# Archimedes_Isil_Mosfet_Kati.net
KiCad netlist of a schematic drawn in Altium Designer
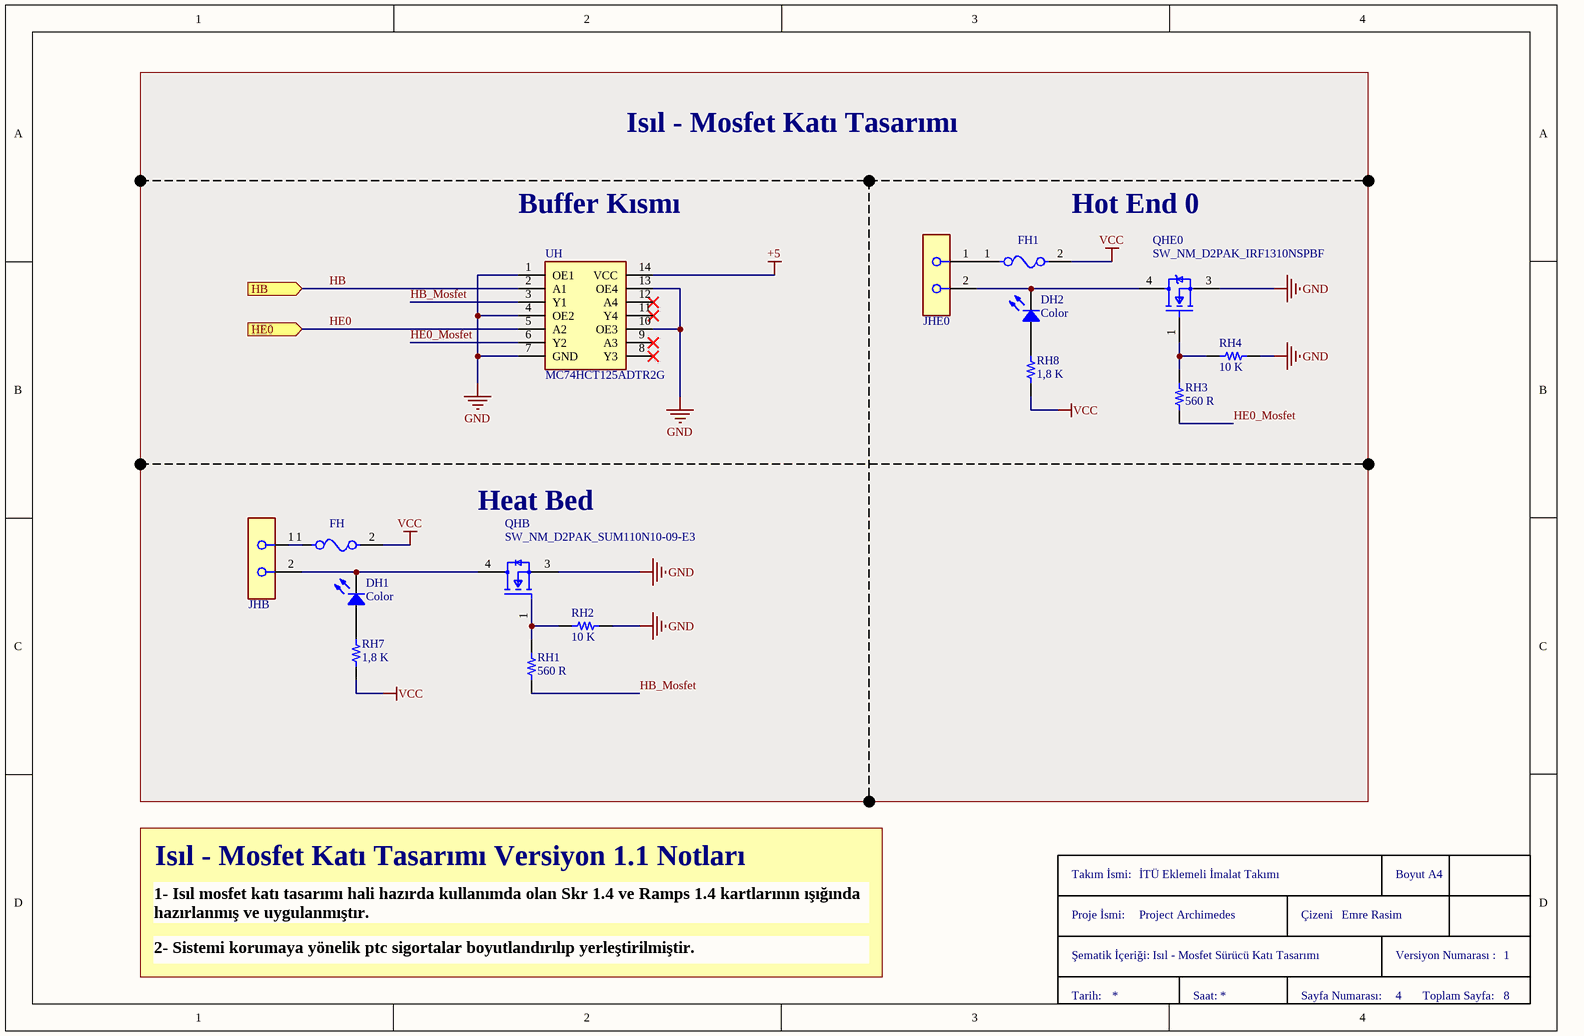
[diagram p0: Archimedes_Isil_Mosfet_Kati.SchDoc]

(export (version "E")
  (design (tool "Eeschema 10.0.6"))
  (components
    (comp (ref "DH1")
      (value "Color")
      (footprint "LED 0805/2012 GREEN")
      (description "LED 805")
      (libsource (lib "Pasifler") (part "LED 805"))
    )
    (comp (ref "DH2")
      (value "Color")
      (footprint "LED 0805/2012 GREEN")
      (description "LED 805")
      (libsource (lib "Pasifler") (part "LED 805"))
    )
    (comp (ref "FH")
      (value "VR_PTC_FRU900-30F")
      (footprint "VR_PTC_FRU900-30F")
      (description "Ptc Fuse with 9 Amper hold and 18 Amper trip values")
      (libsource (lib "EKIM_Team_Main") (part "VR_PTC_FRU900-30F"))
    )
    (comp (ref "FH1")
      (value "VR_PTC_FRU300-30F")
      (footprint "VR_PTC_FRU300-30F")
      (description "Ptc Fuse with 3 Amper hold and 6 Amper Trip values")
      (libsource (lib "EKIM_Team_Main") (part "VR_PTC_FRU300-30F"))
    )
    (comp (ref "JHB")
      (value "Con_5mm_2 lead")
      (footprint "Con_5mm_2lead")
      (description "TERM BLOCK 2POS SIDE ENTRY 5MM")
      (libsource (lib "EKIM_Team_Main") (part "Con_5mm_2 lead"))
    )
    (comp (ref "JHE0")
      (value "Con_5mm_2 lead")
      (footprint "Con_5mm_2lead")
      (description "TERM BLOCK 2POS SIDE ENTRY 5MM")
      (libsource (lib "EKIM_Team_Main") (part "Con_5mm_2 lead"))
    )
    (comp (ref "QHB")
      (value "SW_NM_D2PAK_SUM110N10-09-E3")
      (footprint "SW_D2PAK_Vishay_SUM110N10-09")
      (description "Vishay SUM110N10 nmos with d2pak package , 100 volt and 110 amper values")
      (libsource (lib "EKIM_Team_Main") (part "SW_NM_D2PAK_SUM110N10-09-E3"))
    )
    (comp (ref "QHE0")
      (value "SW_NM_D2PAK_IRF1310NSPBF")
      (footprint "SW_D2PAK_NMOS_IOR_IRF1310NSTRLPBF")
      (description "IOR IRF1310NSPBF NMOS with 100 volt and 42 amper ratings")
      (libsource (lib "EKIM_Team_Main") (part "SW_NM_D2PAK_IRF1310NSPBF"))
    )
    (comp (ref "RH1")
      (value "560 R")
      (footprint "RES 0805/2012")
      (description "560 R ohm Resistor  with 805 pack and %1 tolerance rating")
      (libsource (lib "Pasifler") (part "Resistor 805"))
    )
    (comp (ref "RH2")
      (value "10 K")
      (footprint "RES 0805/2012")
      (description "10 K ohm Resistor  with 805 pack and %1 tolerance rating")
      (libsource (lib "Pasifler") (part "Resistor 805"))
    )
    (comp (ref "RH3")
      (value "560 R")
      (footprint "RES 0805/2012")
      (description "560 R ohm Resistor  with 805 pack and %1 tolerance rating")
      (libsource (lib "Pasifler") (part "Resistor 805"))
    )
    (comp (ref "RH4")
      (value "10 K")
      (footprint "RES 0805/2012")
      (description "10 K ohm Resistor  with 805 pack and %1 tolerance rating")
      (libsource (lib "Pasifler") (part "Resistor 805"))
    )
    (comp (ref "RH7")
      (value "1,8 K")
      (footprint "RES 0805/2012")
      (description "1,8 K ohm Resistor  with 805 pack and %1 tolerance rating")
      (libsource (lib "Pasifler") (part "Resistor 805"))
    )
    (comp (ref "RH8")
      (value "1,8 K")
      (footprint "RES 0805/2012")
      (description "1,8 K K ohm Resistor  with 805 pack and %1 tolerance rating")
      (libsource (lib "Pasifler") (part "Resistor 805"))
    )
    (comp (ref "UH")
      (value "MC74HCT125ADTR2G")
      (footprint "IC_Tssop14_MC74HCT125ADTR2G")
      (description "ON SEMICONDUCTOR - MC74HCT125ADTR2G - Buffer, Non Inverting, 74HCT125A, 2 V to 6 V, TSSOP-14")
      (fields (field (name "MOUSER PART NUMBER") "863-MC74HCT125ADTR2G"))
      (libsource (lib "EKIM_Team_Main") (part "IC_MC74HCT125ADTR2G"))
    )
  )
  (nets
    (net (code "1") (name "+5") (class "Default")
      (node (ref "UH") (pin "14") (pinfunction "VCC_14") (pintype "passive"))
    )
    (net (code "2") (name "/HB") (class "Default")
      (node (ref "UH") (pin "2") (pinfunction "A1_2") (pintype "passive"))
    )
    (net (code "3") (name "/HB_Mosfet") (class "Default")
      (node (ref "RH1") (pin "1") (pinfunction "1_1") (pintype "passive"))
      (node (ref "UH") (pin "3") (pinfunction "Y1_3") (pintype "passive"))
    )
    (net (code "4") (name "/HE0") (class "Default")
      (node (ref "UH") (pin "5") (pinfunction "A2_5") (pintype "passive"))
    )
    (net (code "5") (name "/HE0_Mosfet") (class "Default")
      (node (ref "RH3") (pin "1") (pinfunction "1_1") (pintype "passive"))
      (node (ref "UH") (pin "6") (pinfunction "Y2_6") (pintype "passive"))
    )
    (net (code "6") (name "GND") (class "Default")
      (node (ref "QHB") (pin "3") (pinfunction "S_3") (pintype "passive"))
      (node (ref "QHE0") (pin "3") (pinfunction "S_3") (pintype "passive"))
      (node (ref "RH2") (pin "1") (pinfunction "1_1") (pintype "passive"))
      (node (ref "RH4") (pin "1") (pinfunction "1_1") (pintype "passive"))
      (node (ref "UH") (pin "1") (pinfunction "OE1_1") (pintype "passive"))
      (node (ref "UH") (pin "10") (pinfunction "OE3_10") (pintype "passive"))
      (node (ref "UH") (pin "13") (pinfunction "OE4_13") (pintype "passive"))
      (node (ref "UH") (pin "4") (pinfunction "OE2_4") (pintype "passive"))
      (node (ref "UH") (pin "7") (pinfunction "GND_7") (pintype "passive"))
    )
    (net (code "7") (name "Net-(DH1-Pad1)") (class "Default")
      (node (ref "DH1") (pin "1") (pinfunction "1_1") (pintype "passive"))
      (node (ref "RH7") (pin "1") (pinfunction "1_1") (pintype "passive"))
    )
    (net (code "8") (name "Net-(DH2-Pad1)") (class "Default")
      (node (ref "DH2") (pin "1") (pinfunction "1_1") (pintype "passive"))
      (node (ref "RH8") (pin "1") (pinfunction "1_1") (pintype "passive"))
    )
    (net (code "9") (name "Net-(FH-Pad1)") (class "Default")
      (node (ref "FH") (pin "1") (pinfunction "1_1") (pintype "passive"))
      (node (ref "JHB") (pin "1") (pinfunction "1_1") (pintype "passive"))
    )
    (net (code "10") (name "Net-(FH1-Pad1)") (class "Default")
      (node (ref "FH1") (pin "1") (pinfunction "1_1") (pintype "passive"))
      (node (ref "JHE0") (pin "1") (pinfunction "1_1") (pintype "passive"))
    )
    (net (code "11") (name "Net-(QHB-D)") (class "Default")
      (node (ref "DH1") (pin "2") (pinfunction "2_2") (pintype "passive"))
      (node (ref "JHB") (pin "2") (pinfunction "2_2") (pintype "passive"))
      (node (ref "QHB") (pin "4") (pinfunction "D_4") (pintype "passive"))
    )
    (net (code "12") (name "Net-(QHB-G)") (class "Default")
      (node (ref "QHB") (pin "1") (pinfunction "G_1") (pintype "passive"))
      (node (ref "RH1") (pin "2") (pinfunction "2_2") (pintype "passive"))
      (node (ref "RH2") (pin "2") (pinfunction "2_2") (pintype "passive"))
    )
    (net (code "13") (name "Net-(QHE0-D)") (class "Default")
      (node (ref "DH2") (pin "2") (pinfunction "2_2") (pintype "passive"))
      (node (ref "JHE0") (pin "2") (pinfunction "2_2") (pintype "passive"))
      (node (ref "QHE0") (pin "4") (pinfunction "D_4") (pintype "passive"))
    )
    (net (code "14") (name "Net-(QHE0-G)") (class "Default")
      (node (ref "QHE0") (pin "1") (pinfunction "G_1") (pintype "passive"))
      (node (ref "RH3") (pin "2") (pinfunction "2_2") (pintype "passive"))
      (node (ref "RH4") (pin "2") (pinfunction "2_2") (pintype "passive"))
    )
    (net (code "15") (name "VCC") (class "Default")
      (node (ref "FH") (pin "2") (pinfunction "2_2") (pintype "passive"))
      (node (ref "FH1") (pin "2") (pinfunction "2_2") (pintype "passive"))
      (node (ref "RH7") (pin "2") (pinfunction "2_2") (pintype "passive"))
      (node (ref "RH8") (pin "2") (pinfunction "2_2") (pintype "passive"))
    )
    (net (code "16") (name "unconnected-(UH-A3-Pad9)") (class "Default")
      (node (ref "UH") (pin "9") (pinfunction "A3_9") (pintype "passive+no_connect"))
    )
    (net (code "17") (name "unconnected-(UH-A4-Pad12)") (class "Default")
      (node (ref "UH") (pin "12") (pinfunction "A4_12") (pintype "passive+no_connect"))
    )
    (net (code "18") (name "unconnected-(UH-Y3-Pad8)") (class "Default")
      (node (ref "UH") (pin "8") (pinfunction "Y3_8") (pintype "passive+no_connect"))
    )
    (net (code "19") (name "unconnected-(UH-Y4-Pad11)") (class "Default")
      (node (ref "UH") (pin "11") (pinfunction "Y4_11") (pintype "passive+no_connect"))
    )
  )
)
